# 214_oled_Rev030000.net
KiCad netlist of a schematic drawn in EAGLE
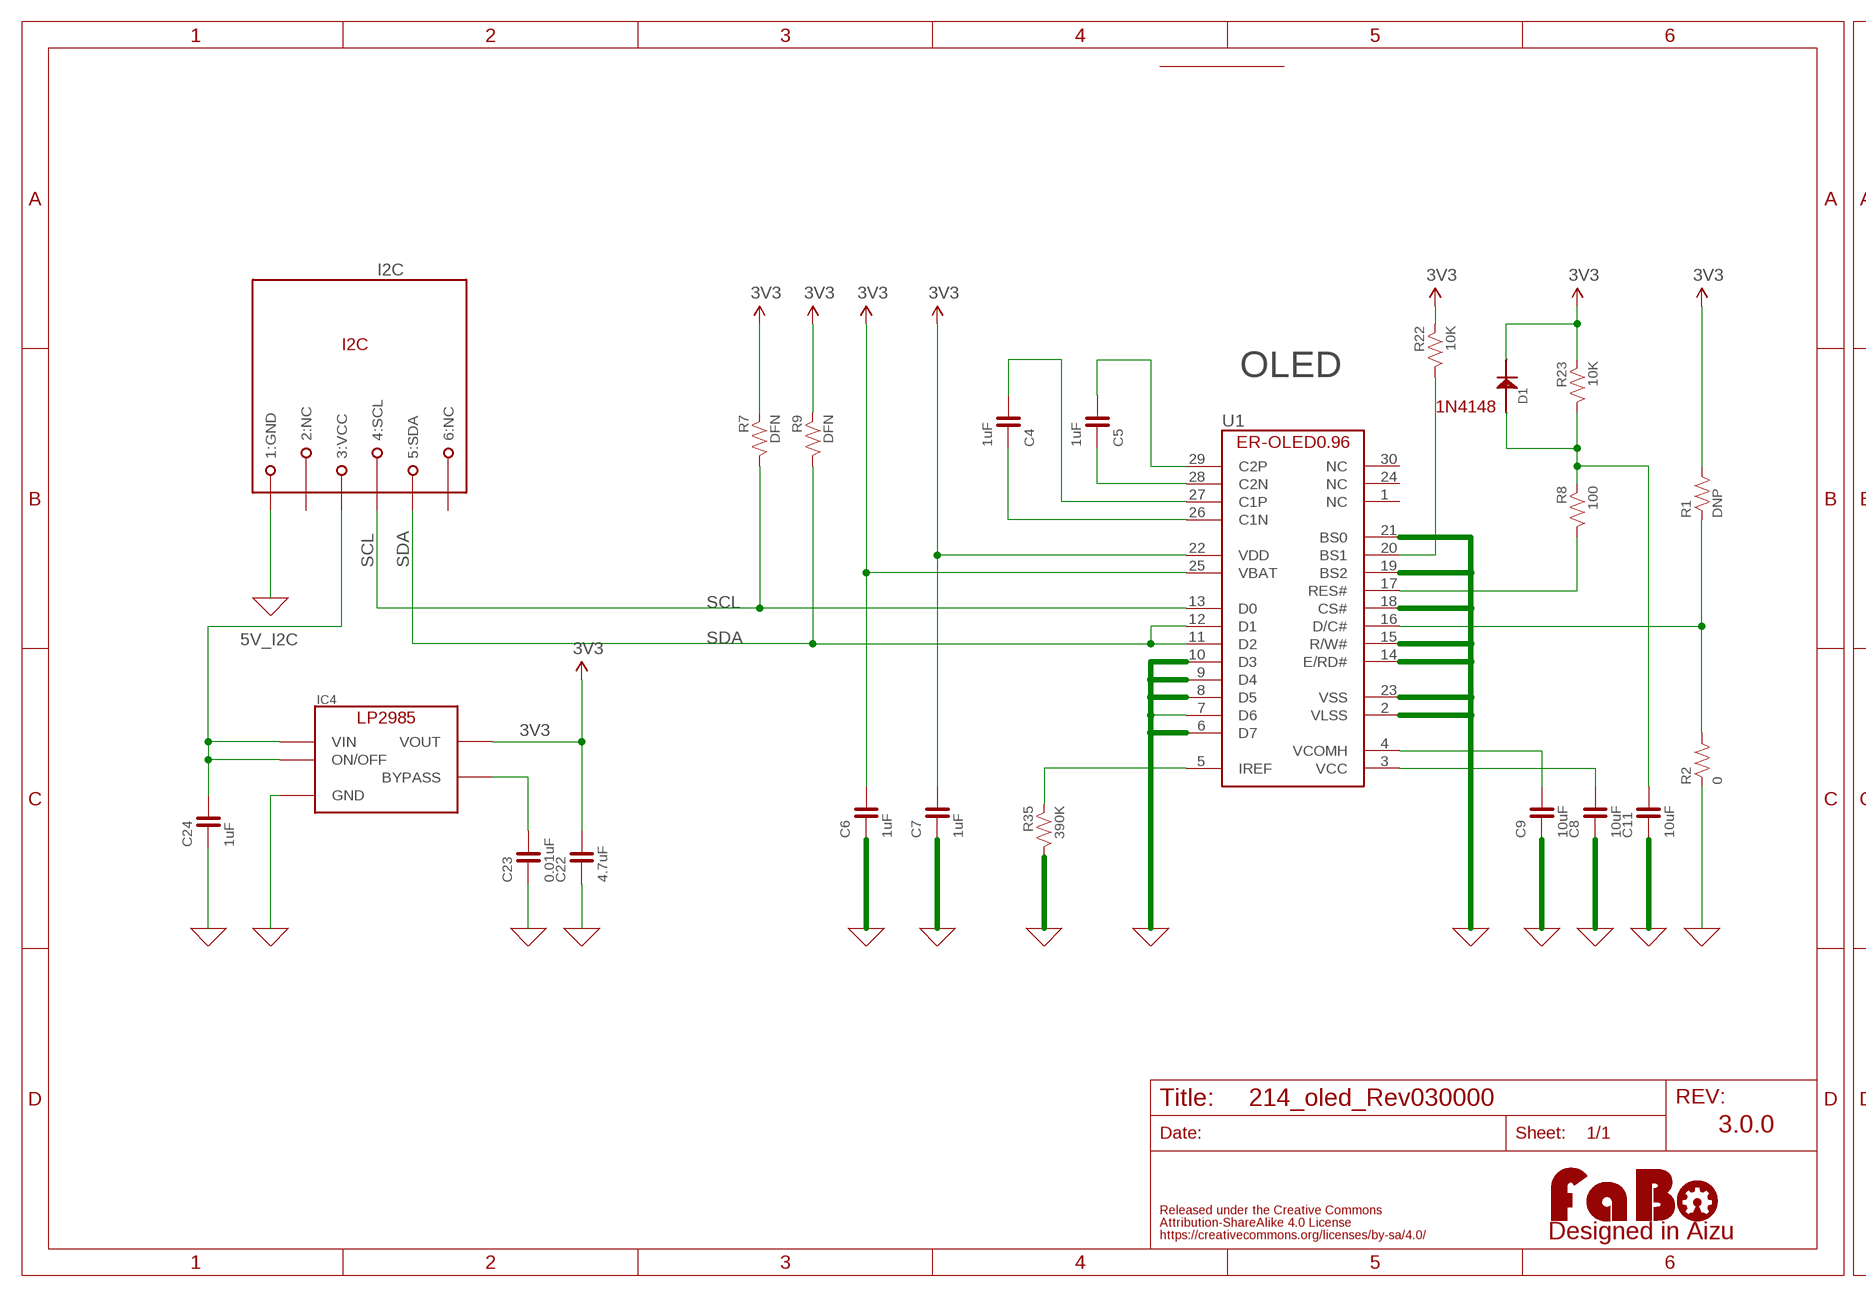
[diagram p0: schematic, sheet 1, part 1 of 2]
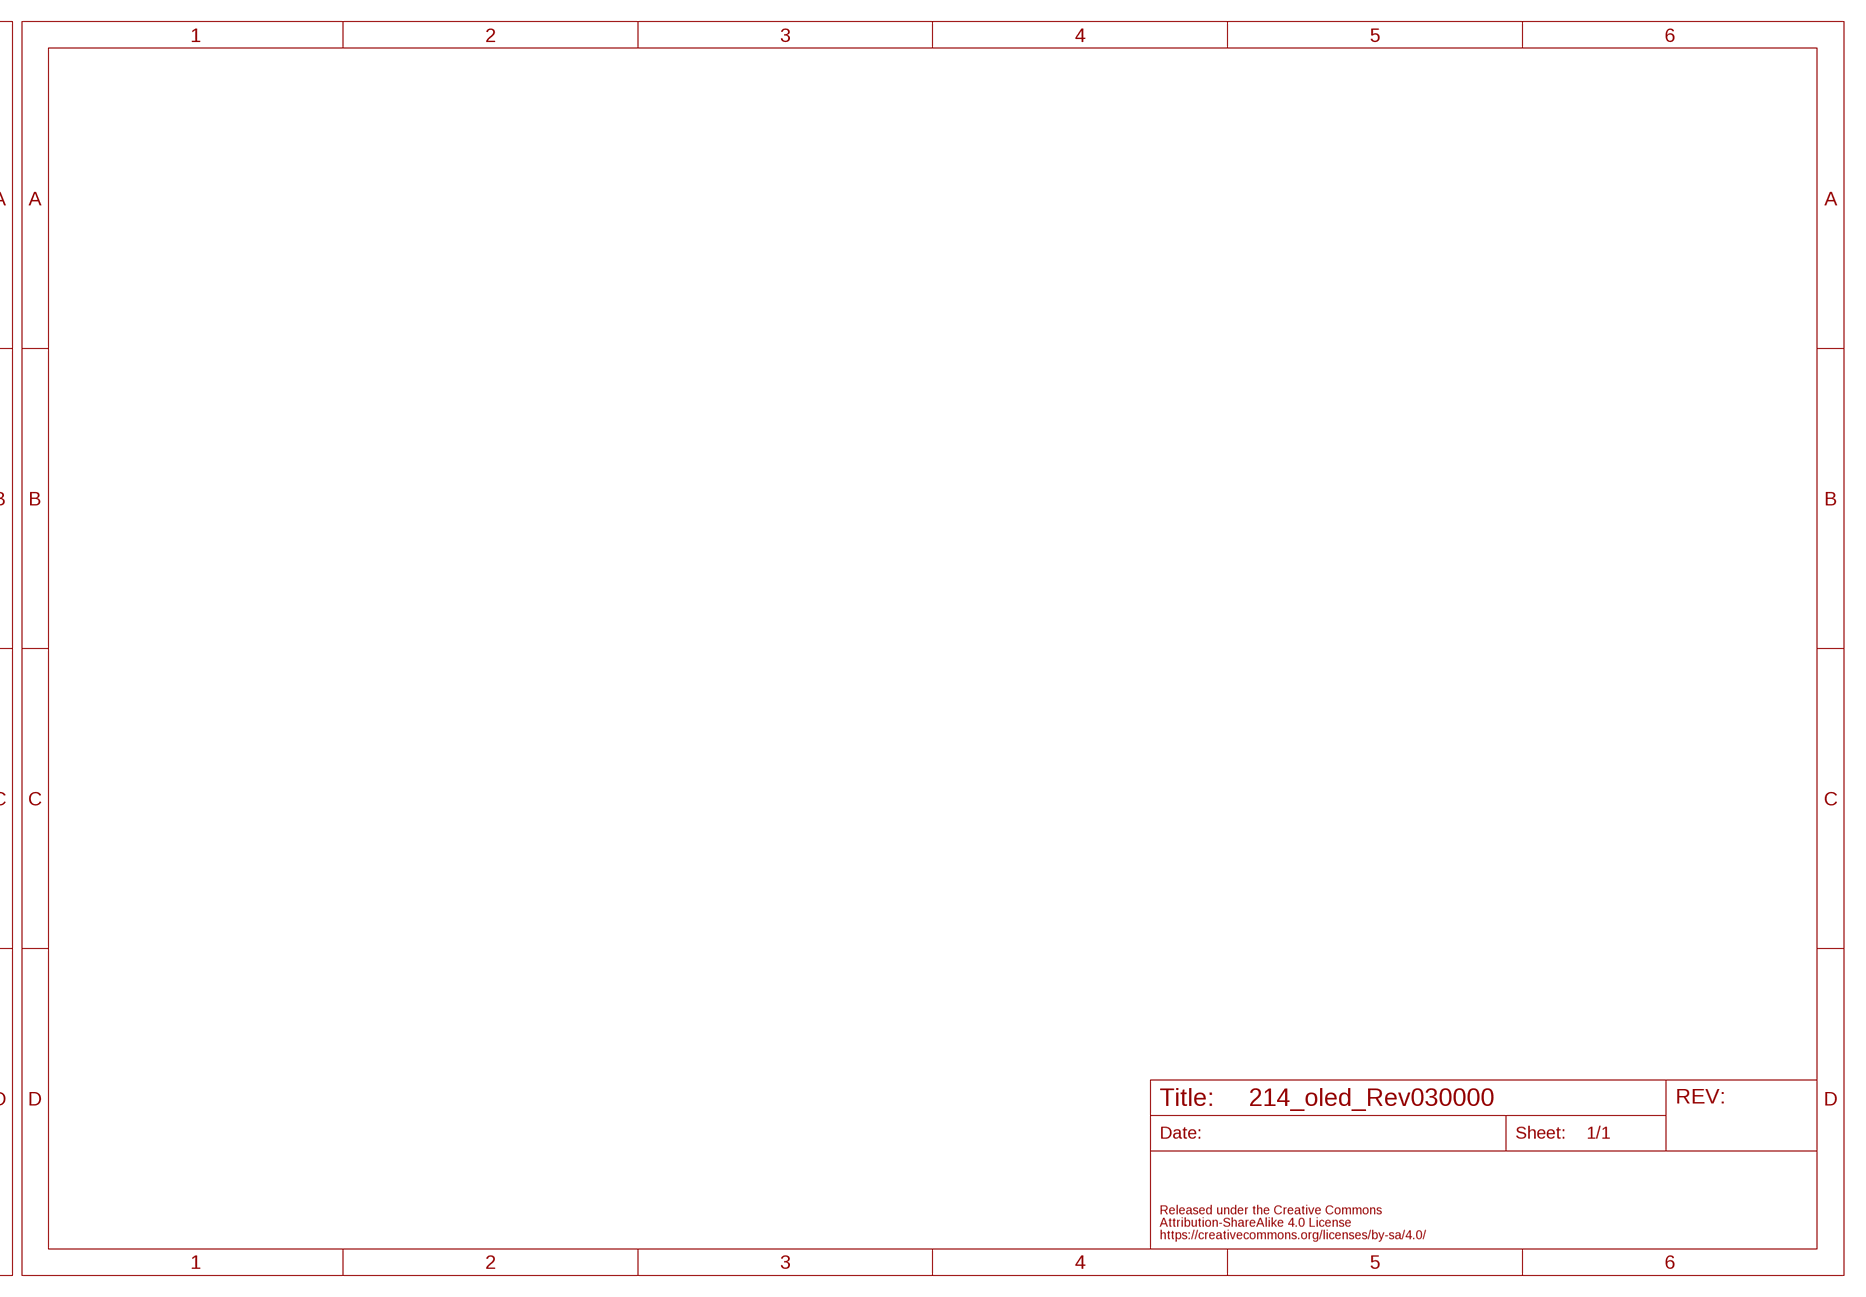
[diagram p1: schematic, sheet 1, part 2 of 2]

(export (version "E")
  (design (tool "Eeschema 10.0.6"))
  (components
    (comp (ref "C4")
      (value "1uF")
      (footprint "eagle-import:0603")
      (libsource (lib "eagle-import") (part "CAPACITOR-0603"))
    )
    (comp (ref "C5")
      (value "1uF")
      (footprint "eagle-import:0603")
      (libsource (lib "eagle-import") (part "CAPACITOR-0603"))
    )
    (comp (ref "C6")
      (value "1uF")
      (footprint "eagle-import:0603")
      (libsource (lib "eagle-import") (part "CAPACITOR-0603"))
    )
    (comp (ref "C7")
      (value "1uF")
      (footprint "eagle-import:0603")
      (libsource (lib "eagle-import") (part "CAPACITOR-0603"))
    )
    (comp (ref "C8")
      (value "10uF")
      (footprint "eagle-import:0603")
      (libsource (lib "eagle-import") (part "CAPACITOR-0603"))
    )
    (comp (ref "C9")
      (value "10uF")
      (footprint "eagle-import:0603")
      (libsource (lib "eagle-import") (part "CAPACITOR-0603"))
    )
    (comp (ref "C11")
      (value "10uF")
      (footprint "eagle-import:0603")
      (libsource (lib "eagle-import") (part "CAPACITOR-0603"))
    )
    (comp (ref "C22")
      (value "4.7uF")
      (footprint "eagle-import:0603")
      (libsource (lib "eagle-import") (part "CAPACITOR-0603"))
    )
    (comp (ref "C23")
      (value "0.01uF")
      (footprint "eagle-import:0603")
      (libsource (lib "eagle-import") (part "CAPACITOR-0603"))
    )
    (comp (ref "C24")
      (value "1uF")
      (footprint "eagle-import:0603")
      (libsource (lib "eagle-import") (part "CAPACITOR-0603"))
    )
    (comp (ref "D1")
      (value "1N4148")
      (footprint "eagle-import:1N4148W")
      (libsource (lib "eagle-import") (part "1N4148"))
    )
    (comp (ref "I2C")
      (value "MODULAR-JACK-6P-RJ11_I2C")
      (footprint "eagle-import:7002-6PXC-X")
      (libsource (lib "eagle-import") (part "MODULAR-JACK-6P-RJ11_I2C"))
    )
    (comp (ref "IC4")
      (value "LP2985-33DBV")
      (footprint "eagle-import:SOT-23-5")
      (libsource (lib "eagle-import") (part "LP2985-33DBV"))
    )
    (comp (ref "LOGO1")
      (value "LOGO_FABO-M_BOTTOM")
      (footprint "eagle-import:LOGO_FABO_M_BOTTOM")
      (libsource (lib "eagle-import") (part "LOGO_FABO-M_BOTTOM"))
    )
    (comp (ref "R1")
      (value "DNP")
      (footprint "eagle-import:0805")
      (fields (field (name "SPICEPREFIX") "R"))
      (libsource (lib "eagle-import") (part "RESISTOR-0805"))
    )
    (comp (ref "R2")
      (value "0")
      (footprint "eagle-import:0805")
      (libsource (lib "eagle-import") (part "RESISTOR-0805"))
    )
    (comp (ref "R7")
      (value "DFN")
      (footprint "eagle-import:0603")
      (libsource (lib "eagle-import") (part "RESISTOR-0603"))
    )
    (comp (ref "R8")
      (value "100")
      (footprint "eagle-import:0603")
      (libsource (lib "eagle-import") (part "RESISTOR-0603"))
    )
    (comp (ref "R9")
      (value "DFN")
      (footprint "eagle-import:0603")
      (libsource (lib "eagle-import") (part "RESISTOR-0603"))
    )
    (comp (ref "R22")
      (value "10K")
      (footprint "eagle-import:0603")
      (libsource (lib "eagle-import") (part "RESISTOR-0603"))
    )
    (comp (ref "R23")
      (value "10K")
      (footprint "eagle-import:0603")
      (libsource (lib "eagle-import") (part "RESISTOR-0603"))
    )
    (comp (ref "R35")
      (value "390K")
      (footprint "eagle-import:0603")
      (libsource (lib "eagle-import") (part "RESISTOR-0603"))
    )
    (comp (ref "U1")
      (value "ER-OLED0.96-1ER-CON30HT-1")
      (footprint "eagle-import:ER-CON30HT-1")
      (libsource (lib "eagle-import") (part "ER-OLED0.96-1ER-CON30HT-1"))
    )
  )
  (nets
    (net (code "1") (name "/5V_I2C") (class "Default")
      (node (ref "C24") (pin "2") (pinfunction "2_2") (pintype "passive"))
      (node (ref "I2C") (pin "3") (pinfunction "3:VCC_3") (pintype "power_in"))
      (node (ref "IC4") (pin "1") (pinfunction "VIN_1") (pintype "input"))
      (node (ref "IC4") (pin "3") (pinfunction "ON/OFF_3") (pintype "input"))
    )
    (net (code "2") (name "/SCL") (class "Default")
      (node (ref "I2C") (pin "4") (pinfunction "4:SCL_4") (pintype "open_collector"))
      (node (ref "R7") (pin "2") (pinfunction "2_2") (pintype "bidirectional"))
      (node (ref "U1") (pin "13") (pinfunction "D0_13") (pintype "bidirectional"))
    )
    (net (code "3") (name "/SDA") (class "Default")
      (node (ref "I2C") (pin "5") (pinfunction "5:SDA_5") (pintype "open_collector"))
      (node (ref "R9") (pin "2") (pinfunction "2_2") (pintype "bidirectional"))
      (node (ref "U1") (pin "11") (pinfunction "D2_11") (pintype "bidirectional"))
      (node (ref "U1") (pin "12") (pinfunction "D1_12") (pintype "bidirectional"))
    )
    (net (code "4") (name "3V3") (class "Default")
      (node (ref "C22") (pin "2") (pinfunction "2_2") (pintype "passive"))
      (node (ref "C6") (pin "2") (pinfunction "2_2") (pintype "passive"))
      (node (ref "C7") (pin "2") (pinfunction "2_2") (pintype "passive"))
      (node (ref "D1") (pin "CATHODE") (pinfunction "CATHODE_CATHODE") (pintype "bidirectional"))
      (node (ref "IC4") (pin "5") (pinfunction "VOUT_5") (pintype "output"))
      (node (ref "R1") (pin "2") (pinfunction "2_2") (pintype "bidirectional"))
      (node (ref "R22") (pin "1") (pinfunction "1_1") (pintype "bidirectional"))
      (node (ref "R23") (pin "1") (pinfunction "1_1") (pintype "bidirectional"))
      (node (ref "R7") (pin "1") (pinfunction "1_1") (pintype "bidirectional"))
      (node (ref "R9") (pin "1") (pinfunction "1_1") (pintype "bidirectional"))
      (node (ref "U1") (pin "22") (pinfunction "VDD_22") (pintype "bidirectional"))
      (node (ref "U1") (pin "25") (pinfunction "VBAT_25") (pintype "bidirectional"))
    )
    (net (code "5") (name "GND") (class "Default")
      (node (ref "C11") (pin "1") (pinfunction "1_1") (pintype "passive"))
      (node (ref "C22") (pin "1") (pinfunction "1_1") (pintype "passive"))
      (node (ref "C23") (pin "1") (pinfunction "1_1") (pintype "passive"))
      (node (ref "C24") (pin "1") (pinfunction "1_1") (pintype "passive"))
      (node (ref "C6") (pin "1") (pinfunction "1_1") (pintype "passive"))
      (node (ref "C7") (pin "1") (pinfunction "1_1") (pintype "passive"))
      (node (ref "C8") (pin "1") (pinfunction "1_1") (pintype "passive"))
      (node (ref "C9") (pin "1") (pinfunction "1_1") (pintype "passive"))
      (node (ref "I2C") (pin "1") (pinfunction "1:GND_1") (pintype "power_in"))
      (node (ref "IC4") (pin "2") (pinfunction "GND_2") (pintype "power_in"))
      (node (ref "R2") (pin "1") (pinfunction "1_1") (pintype "bidirectional"))
      (node (ref "R35") (pin "2") (pinfunction "2_2") (pintype "bidirectional"))
      (node (ref "U1") (pin "10") (pinfunction "D3_10") (pintype "bidirectional"))
      (node (ref "U1") (pin "14") (pinfunction "E/RD#_14") (pintype "bidirectional"))
      (node (ref "U1") (pin "15") (pinfunction "R/W#_15") (pintype "bidirectional"))
      (node (ref "U1") (pin "18") (pinfunction "CS#_18") (pintype "bidirectional"))
      (node (ref "U1") (pin "19") (pinfunction "BS2_19") (pintype "bidirectional"))
      (node (ref "U1") (pin "2") (pinfunction "VLSS_2") (pintype "bidirectional"))
      (node (ref "U1") (pin "21") (pinfunction "BS0_21") (pintype "bidirectional"))
      (node (ref "U1") (pin "23") (pinfunction "VSS_23") (pintype "bidirectional"))
      (node (ref "U1") (pin "6") (pinfunction "D7_6") (pintype "bidirectional"))
      (node (ref "U1") (pin "7") (pinfunction "D6_7") (pintype "bidirectional"))
      (node (ref "U1") (pin "8") (pinfunction "D5_8") (pintype "bidirectional"))
      (node (ref "U1") (pin "9") (pinfunction "D4_9") (pintype "bidirectional"))
    )
    (net (code "6") (name "Net-(C11-Pad2)") (class "Default")
      (node (ref "C11") (pin "2") (pinfunction "2_2") (pintype "passive"))
      (node (ref "D1") (pin "ANODE") (pinfunction "ANODE_ANODE") (pintype "bidirectional"))
      (node (ref "R23") (pin "2") (pinfunction "2_2") (pintype "bidirectional"))
      (node (ref "R8") (pin "1") (pinfunction "1_1") (pintype "bidirectional"))
    )
    (net (code "7") (name "Net-(IC4-BYPASS)") (class "Default")
      (node (ref "C23") (pin "2") (pinfunction "2_2") (pintype "passive"))
      (node (ref "IC4") (pin "4") (pinfunction "BYPASS_4") (pintype "bidirectional"))
    )
    (net (code "8") (name "Net-(U1-BS1)") (class "Default")
      (node (ref "R22") (pin "2") (pinfunction "2_2") (pintype "bidirectional"))
      (node (ref "U1") (pin "20") (pinfunction "BS1_20") (pintype "bidirectional"))
    )
    (net (code "9") (name "Net-(U1-C1N)") (class "Default")
      (node (ref "C4") (pin "1") (pinfunction "1_1") (pintype "passive"))
      (node (ref "U1") (pin "26") (pinfunction "C1N_26") (pintype "bidirectional"))
    )
    (net (code "10") (name "Net-(U1-C1P)") (class "Default")
      (node (ref "C4") (pin "2") (pinfunction "2_2") (pintype "passive"))
      (node (ref "U1") (pin "27") (pinfunction "C1P_27") (pintype "bidirectional"))
    )
    (net (code "11") (name "Net-(U1-C2N)") (class "Default")
      (node (ref "C5") (pin "1") (pinfunction "1_1") (pintype "passive"))
      (node (ref "U1") (pin "28") (pinfunction "C2N_28") (pintype "bidirectional"))
    )
    (net (code "12") (name "Net-(U1-C2P)") (class "Default")
      (node (ref "C5") (pin "2") (pinfunction "2_2") (pintype "passive"))
      (node (ref "U1") (pin "29") (pinfunction "C2P_29") (pintype "bidirectional"))
    )
    (net (code "13") (name "Net-(U1-D{slash}C#)") (class "Default")
      (node (ref "R1") (pin "1") (pinfunction "1_1") (pintype "bidirectional"))
      (node (ref "R2") (pin "2") (pinfunction "2_2") (pintype "bidirectional"))
      (node (ref "U1") (pin "16") (pinfunction "D/C#_16") (pintype "bidirectional"))
    )
    (net (code "14") (name "Net-(U1-IREF)") (class "Default")
      (node (ref "R35") (pin "1") (pinfunction "1_1") (pintype "bidirectional"))
      (node (ref "U1") (pin "5") (pinfunction "IREF_5") (pintype "bidirectional"))
    )
    (net (code "15") (name "Net-(U1-RES#)") (class "Default")
      (node (ref "R8") (pin "2") (pinfunction "2_2") (pintype "bidirectional"))
      (node (ref "U1") (pin "17") (pinfunction "RES#_17") (pintype "bidirectional"))
    )
    (net (code "16") (name "Net-(U1-VCC)") (class "Default")
      (node (ref "C8") (pin "2") (pinfunction "2_2") (pintype "passive"))
      (node (ref "U1") (pin "3") (pinfunction "VCC_3") (pintype "bidirectional"))
    )
    (net (code "17") (name "Net-(U1-VCOMH)") (class "Default")
      (node (ref "C9") (pin "2") (pinfunction "2_2") (pintype "passive"))
      (node (ref "U1") (pin "4") (pinfunction "VCOMH_4") (pintype "bidirectional"))
    )
    (net (code "18") (name "unconnected-(I2C-2:NC-Pad2)") (class "Default")
      (node (ref "I2C") (pin "2") (pinfunction "2:NC_2") (pintype "no_connect"))
    )
    (net (code "19") (name "unconnected-(I2C-6:NC-Pad6)") (class "Default")
      (node (ref "I2C") (pin "6") (pinfunction "6:NC_6") (pintype "no_connect"))
    )
    (net (code "20") (name "unconnected-(U1-NC-Pad1)") (class "Default")
      (node (ref "U1") (pin "1") (pinfunction "NC_1") (pintype "bidirectional"))
    )
    (net (code "21") (name "unconnected-(U1-NC-Pad24)") (class "Default")
      (node (ref "U1") (pin "24") (pinfunction "NC_24") (pintype "bidirectional"))
    )
    (net (code "22") (name "unconnected-(U1-NC-Pad30)") (class "Default")
      (node (ref "U1") (pin "30") (pinfunction "NC_30") (pintype "bidirectional"))
    )
  )
)
